# Block_Diagram.net
KiCad netlist of a schematic drawn in Altium Designer
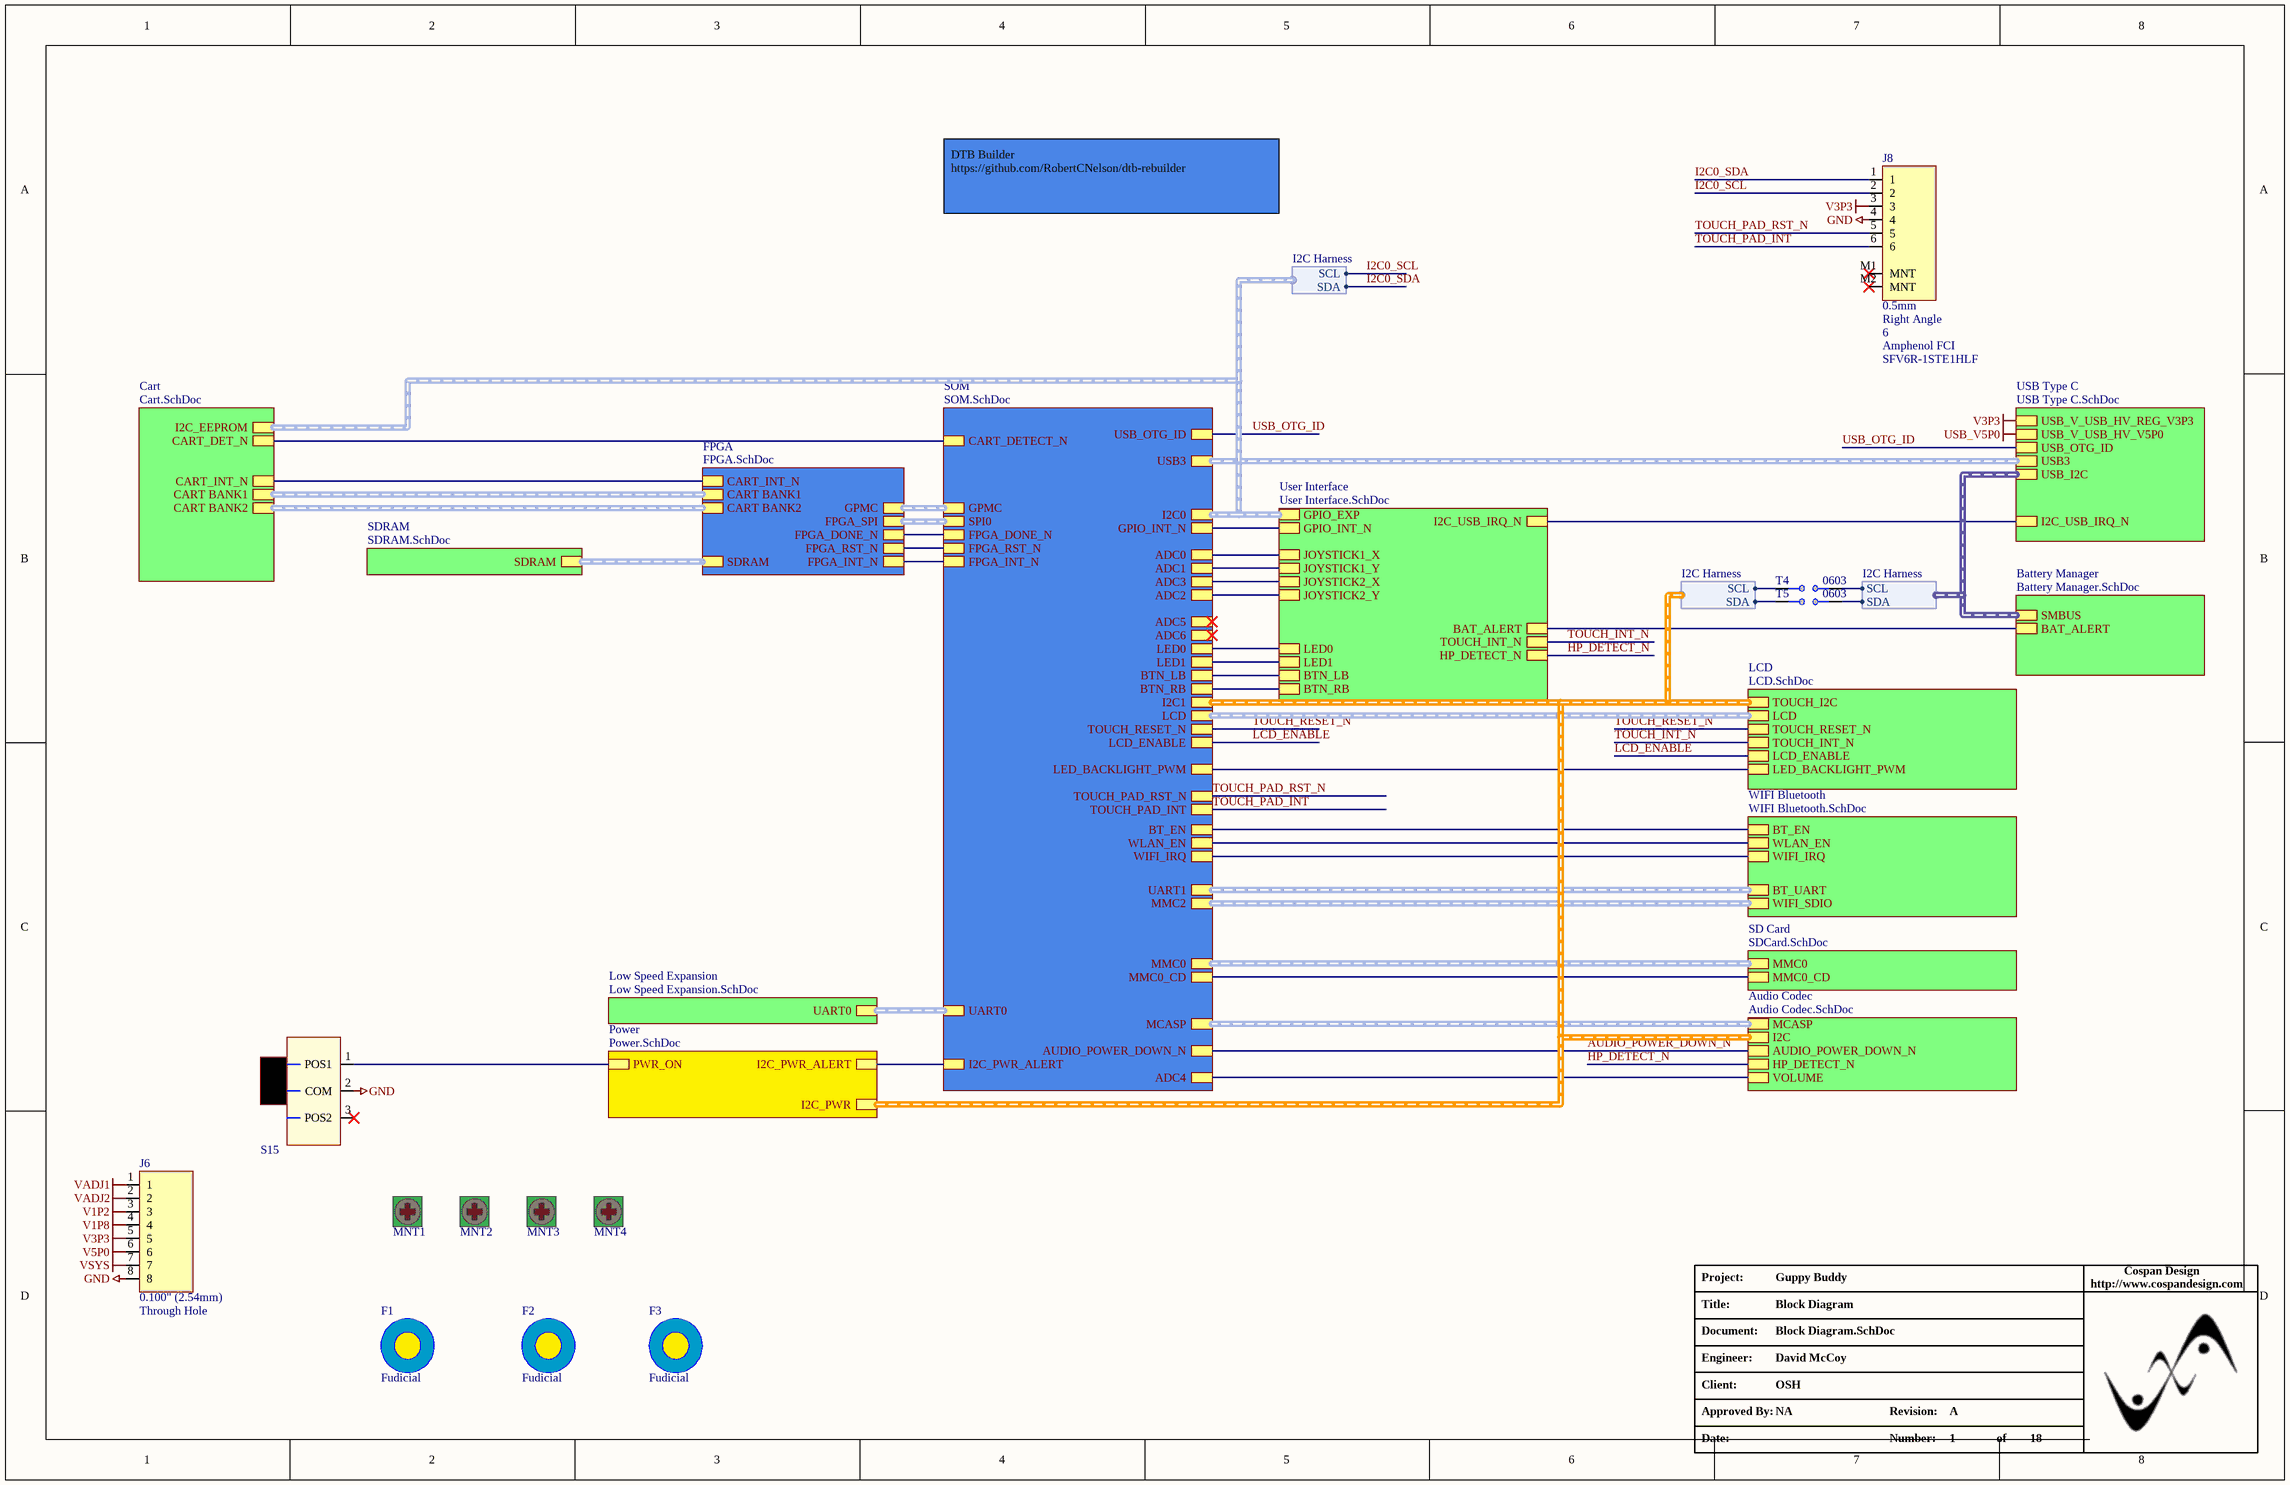
[diagram p0: Block Diagram.SchDoc]

(export (version "E")
  (design (tool "Eeschema 10.0.6"))
  (components
    (comp (ref "F1")
      (value "Fudicial")
      (footprint "FIDUCIAL ROUND")
      (libsource (lib "Main Library") (part "F_FUDICIAL"))
    )
    (comp (ref "F2")
      (value "Fudicial")
      (footprint "FIDUCIAL ROUND")
      (libsource (lib "Main Library") (part "F_FUDICIAL"))
    )
    (comp (ref "F3")
      (value "Fudicial")
      (footprint "FIDUCIAL ROUND")
      (libsource (lib "Main Library") (part "F_FUDICIAL"))
    )
    (comp (ref "J6")
      (value "1 X 8 HOLES")
      (footprint "HDR_1X8 - HOLE")
      (fields (field (name "PITCH") "0.100\" (2.54mm)") (field (name "MOUNTING TYPE") "Through Hole"))
      (libsource (lib "Main Library") (part "J_HDR1X8_HOLES"))
    )
    (comp (ref "J8")
      (value "J_FFC_CONN_RA_6PIN")
      (footprint "FFC_6PIN")
      (description "CONN FFC BOTTOM 6POS 0.50MM R/A")
      (fields
        (field (name "PITCH") "0.5mm")
        (field (name "ORIENTATION") "Right Angle")
        (field (name "NUMBER OF CONTACTS") "6")
        (field (name "MANUFACTURER 1") "Amphenol FCI")
        (field (name "MANUFACTURER PART NUMBER 1") "SFV6R-1STE1HLF")
      )
      (libsource (lib "Cospan Design") (part "J_FFC_CONN_RA_6PIN"))
    )
    (comp (ref "MNT1")
      (value "Mounting Hole")
      (footprint "MNT_4-40")
      (libsource (lib "Cospan Design") (part "MNT?"))
    )
    (comp (ref "MNT2")
      (value "Mounting Hole")
      (footprint "MNT_4-40")
      (libsource (lib "Cospan Design") (part "MNT?"))
    )
    (comp (ref "MNT3")
      (value "Mounting Hole")
      (footprint "MNT_4-40")
      (libsource (lib "Cospan Design") (part "MNT?"))
    )
    (comp (ref "MNT4")
      (value "Mounting Hole")
      (footprint "MNT_4-40")
      (libsource (lib "Cospan Design") (part "MNT?"))
    )
    (comp (ref "S15")
      (value "Micro Slide Switch")
      (footprint "PCM_SMD_SWITCH")
      (description "SWITCH SLIDE SPDT 300MA 6V")
      (fields
        (field (name "MANUFACTURER") "C&K Components")
        (field (name "MANUFACTURER PART NUMBER") "PCM12SMTR")
      )
      (libsource (lib "Cospan Design") (part "S_MICRO_SLIDE_SWITCH_ON_OFF"))
    )
    (comp (ref "T4")
      (value "Place Solder Bridge to Enable")
      (footprint "ERA-0603-SOLDER_JUMPER")
      (description "SOLDER_JUMPER PAD")
      (fields (field (name "CASE") "0603"))
      (libsource (lib "Main Library") (part "T_0603_JUMPER_PAD"))
    )
    (comp (ref "T5")
      (value "Place Solder Bridge to Enable")
      (footprint "ERA-0603-SOLDER_JUMPER")
      (description "SOLDER_JUMPER PAD")
      (fields (field (name "CASE") "0603"))
      (libsource (lib "Main Library") (part "T_0603_JUMPER_PAD"))
    )
  )
  (nets
    (net (code "27") (name "/I2C0_SCL") (class "Default")
      (node (ref "J8") (pin "2") (pinfunction "2_2") (pintype "passive"))
    )
    (net (code "28") (name "/I2C0_SDA") (class "Default")
      (node (ref "J8") (pin "1") (pinfunction "1_1") (pintype "passive"))
    )
    (net (code "40") (name "/PWR_ON") (class "Default")
      (node (ref "S15") (pin "1") (pinfunction "POS1_1") (pintype "passive"))
    )
    (net (code "43") (name "/TOUCH_PAD_INT") (class "Default")
      (node (ref "J8") (pin "6") (pinfunction "6_6") (pintype "passive"))
    )
    (net (code "44") (name "/TOUCH_PAD_RST_N") (class "Default")
      (node (ref "J8") (pin "5") (pinfunction "5_5") (pintype "passive"))
    )
    (net (code "52") (name "GND") (class "Default")
      (node (ref "J6") (pin "8") (pinfunction "8_8") (pintype "passive"))
      (node (ref "J8") (pin "4") (pinfunction "4_4") (pintype "passive"))
      (node (ref "S15") (pin "2") (pinfunction "COM_2") (pintype "passive"))
    )
    (net (code "54") (name "V1P2") (class "Default")
      (node (ref "J6") (pin "3") (pinfunction "3_3") (pintype "passive"))
    )
    (net (code "55") (name "V1P8") (class "Default")
      (node (ref "J6") (pin "4") (pinfunction "4_4") (pintype "passive"))
    )
    (net (code "56") (name "V3P3") (class "Default")
      (node (ref "J6") (pin "5") (pinfunction "5_5") (pintype "passive"))
      (node (ref "J8") (pin "3") (pinfunction "3_3") (pintype "passive"))
    )
    (net (code "57") (name "V5P0") (class "Default")
      (node (ref "J6") (pin "6") (pinfunction "6_6") (pintype "passive"))
    )
    (net (code "58") (name "VADJ1") (class "Default")
      (node (ref "J6") (pin "1") (pinfunction "1_1") (pintype "passive"))
    )
    (net (code "59") (name "VADJ2") (class "Default")
      (node (ref "J6") (pin "2") (pinfunction "2_2") (pintype "passive"))
    )
    (net (code "60") (name "VSYS") (class "Default")
      (node (ref "J6") (pin "7") (pinfunction "7_7") (pintype "passive"))
    )
    (net (code "61") (name "unconnected-(J8-MNT-PadM1)") (class "Default")
      (node (ref "J8") (pin "M1") (pinfunction "MNT_M1") (pintype "passive+no_connect"))
    )
    (net (code "62") (name "unconnected-(J8-MNT-PadM2)") (class "Default")
      (node (ref "J8") (pin "M2") (pinfunction "MNT_M2") (pintype "passive+no_connect"))
    )
    (net (code "63") (name "unconnected-(S15-POS2-Pad3)") (class "Default")
      (node (ref "S15") (pin "3") (pinfunction "POS2_3") (pintype "passive+no_connect"))
    )
    (net (code "64") (name "unconnected-(T4-Pad1)") (class "Default")
      (node (ref "T4") (pin "1") (pinfunction "1_1") (pintype "passive"))
    )
    (net (code "65") (name "unconnected-(T4-Pad2)") (class "Default")
      (node (ref "T4") (pin "2") (pinfunction "2_2") (pintype "passive"))
    )
    (net (code "66") (name "unconnected-(T5-Pad1)") (class "Default")
      (node (ref "T5") (pin "1") (pinfunction "1_1") (pintype "passive"))
    )
    (net (code "67") (name "unconnected-(T5-Pad2)") (class "Default")
      (node (ref "T5") (pin "2") (pinfunction "2_2") (pintype "passive"))
    )
  )
)
